# Zeus_v2.net
KiCad netlist of a schematic drawn in EAGLE
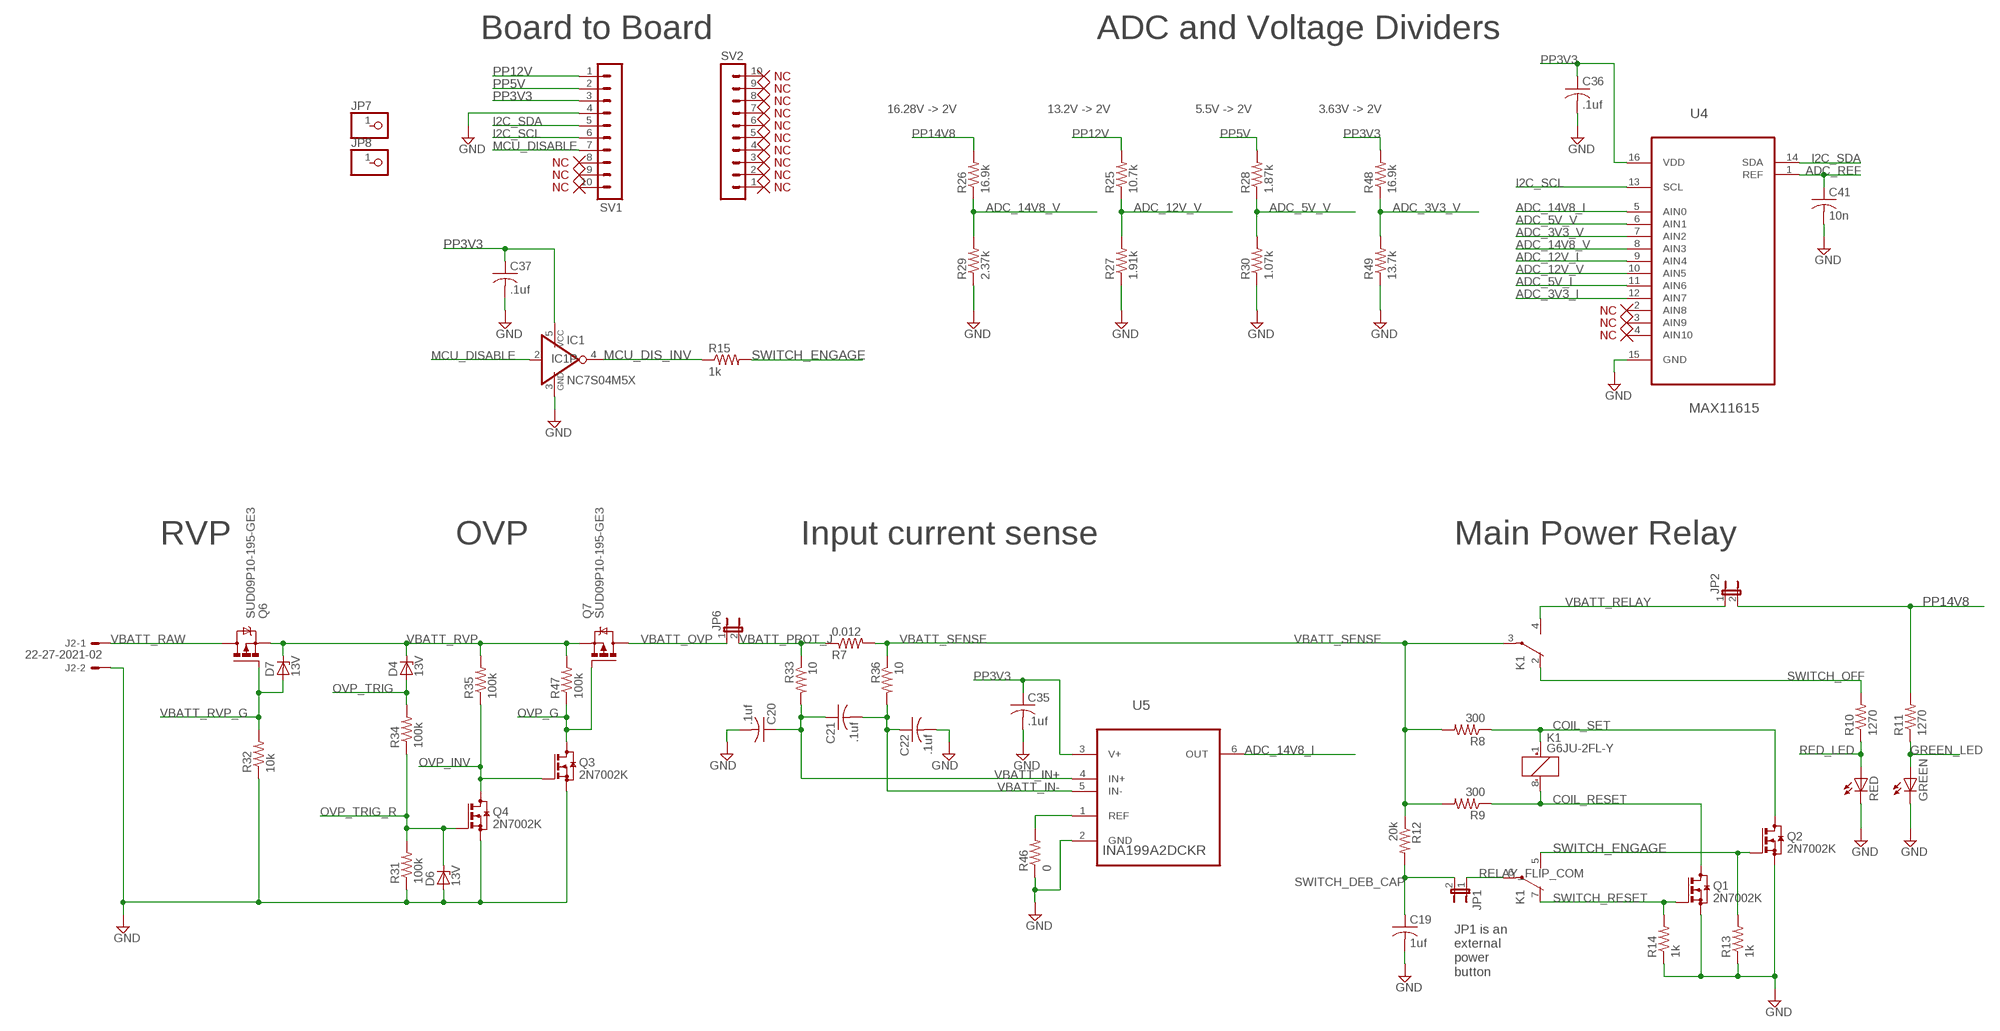
[diagram p0: schematic, sheet 1, part 1 of 2]
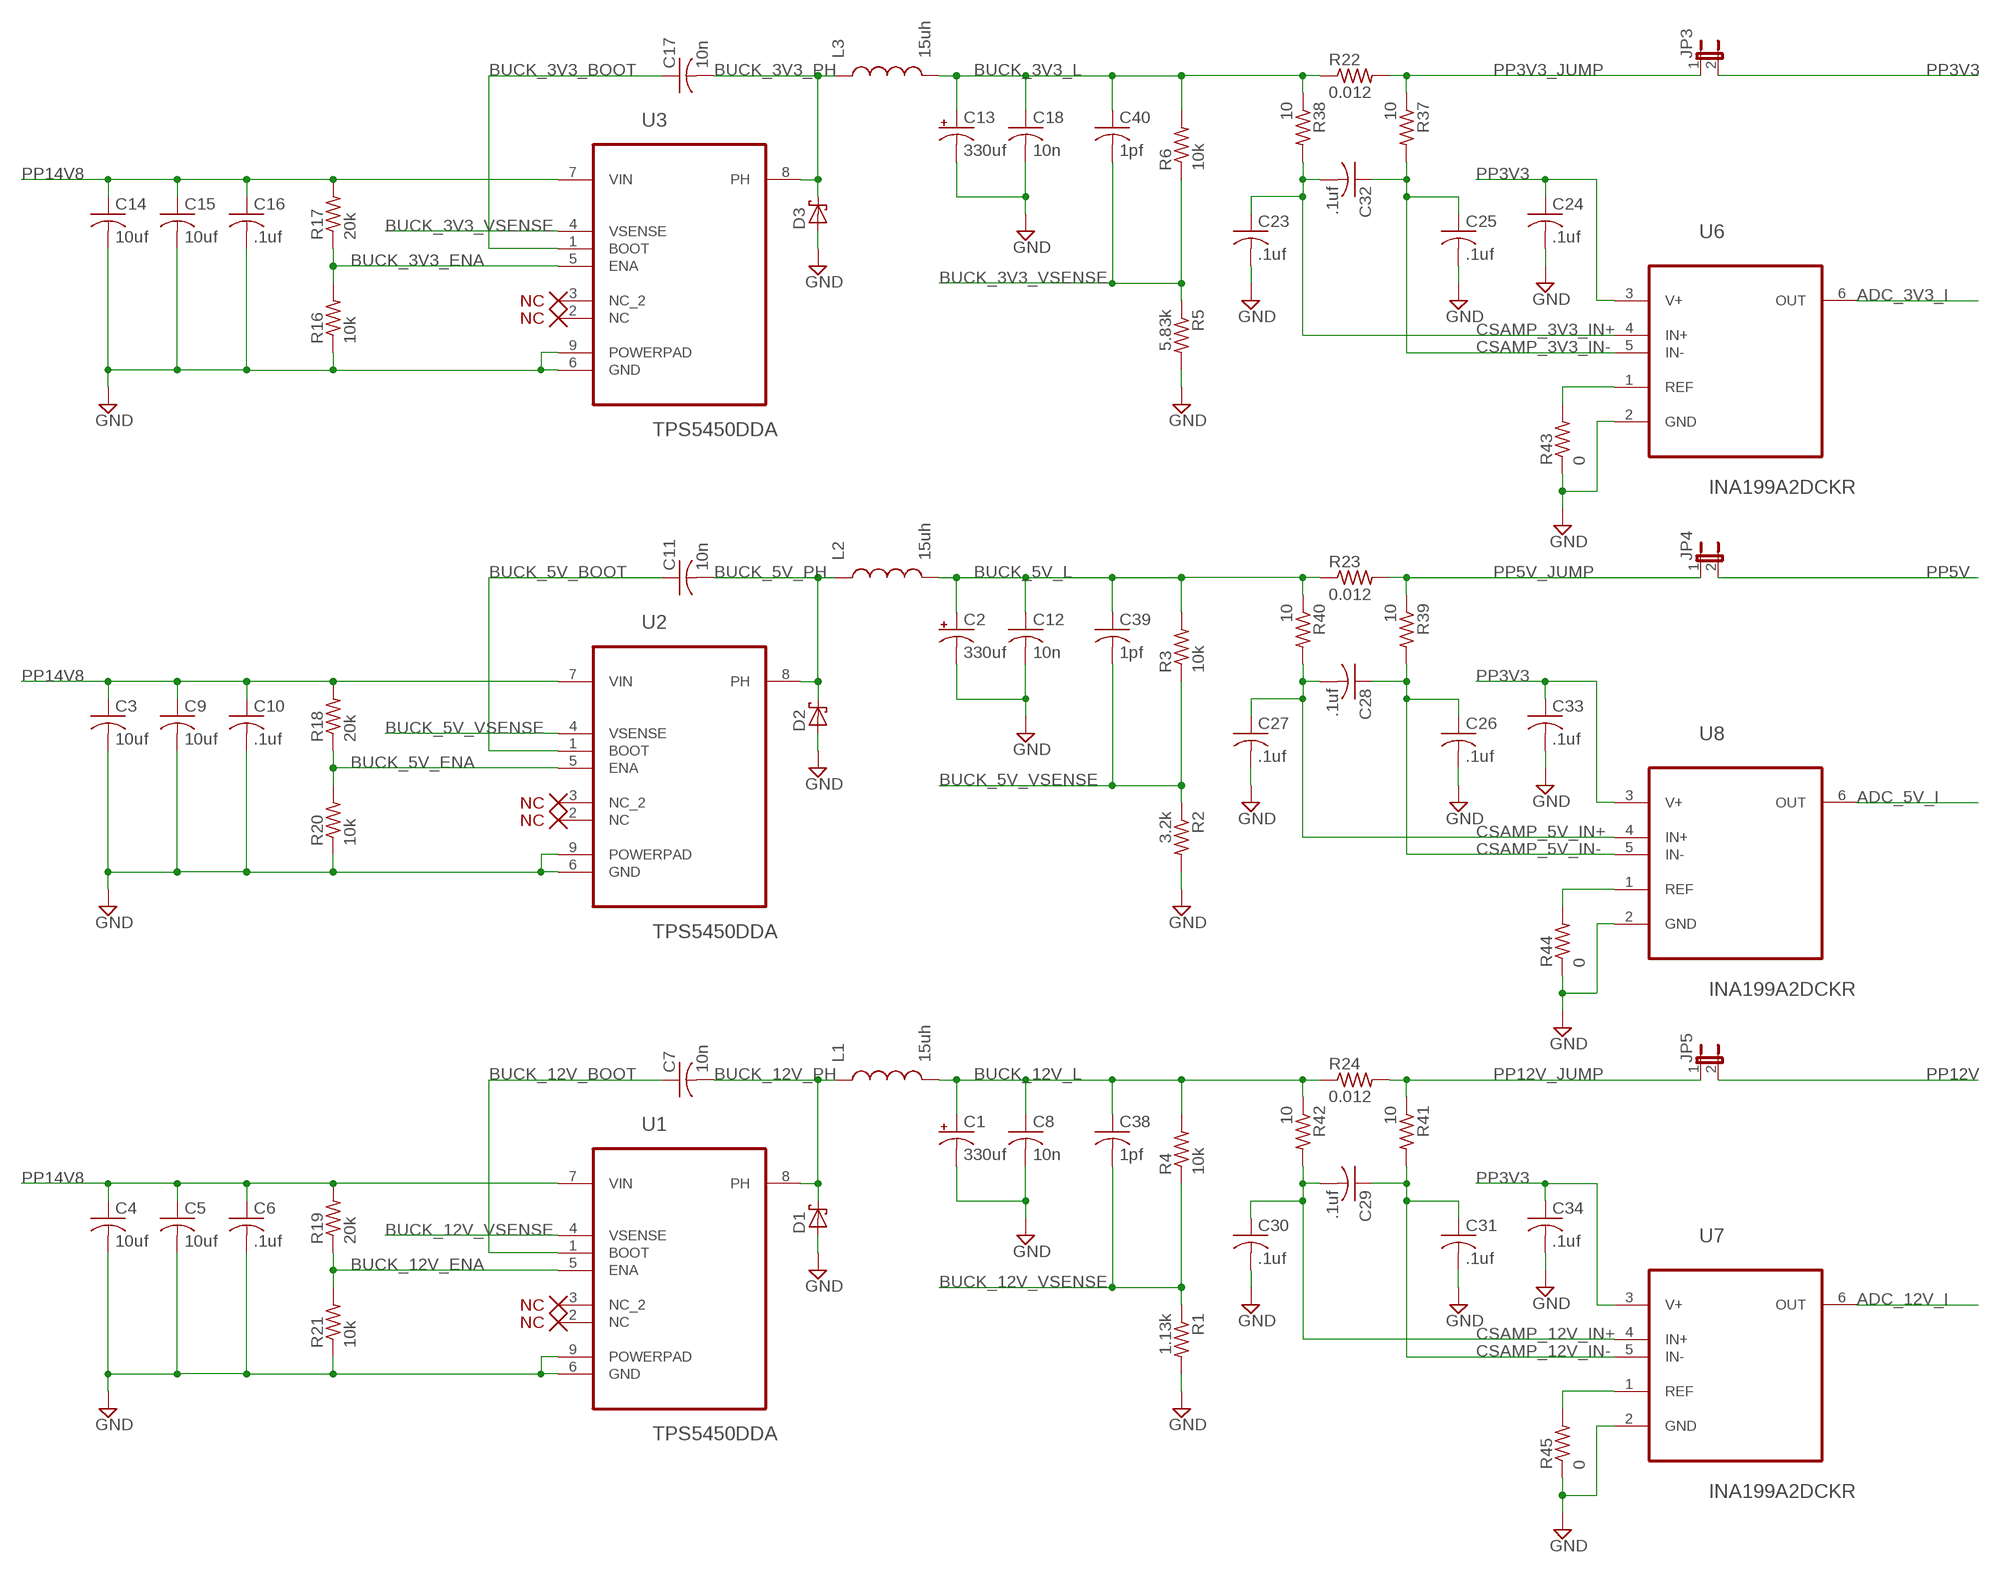
[diagram p1: schematic, sheet 1, part 2 of 2]

(export (version "E")
  (design (tool "Eeschema 10.0.6"))
  (components
    (comp (ref "C1")
      (value "330uf")
      (footprint "eagle-import:153CLV-0605")
      (libsource (lib "eagle-import") (part "CPOL-US153CLV-0605"))
    )
    (comp (ref "C2")
      (value "330uf")
      (footprint "eagle-import:153CLV-0605")
      (libsource (lib "eagle-import") (part "CPOL-US153CLV-0605"))
    )
    (comp (ref "C3")
      (value "10uf")
      (footprint "eagle-import:C1206")
      (libsource (lib "eagle-import") (part "C-USC1206"))
    )
    (comp (ref "C4")
      (value "10uf")
      (footprint "eagle-import:C1206")
      (libsource (lib "eagle-import") (part "C-USC1206"))
    )
    (comp (ref "C5")
      (value "10uf")
      (footprint "eagle-import:C1206")
      (libsource (lib "eagle-import") (part "C-USC1206"))
    )
    (comp (ref "C6")
      (value ".1uf")
      (footprint "eagle-import:C0402")
      (libsource (lib "eagle-import") (part "C-USC0402"))
    )
    (comp (ref "C7")
      (value "10n")
      (footprint "eagle-import:C0402")
      (libsource (lib "eagle-import") (part "C-USC0402"))
    )
    (comp (ref "C8")
      (value "10n")
      (footprint "eagle-import:C0402")
      (libsource (lib "eagle-import") (part "C-USC0402"))
    )
    (comp (ref "C9")
      (value "10uf")
      (footprint "eagle-import:C1206")
      (libsource (lib "eagle-import") (part "C-USC1206"))
    )
    (comp (ref "C10")
      (value ".1uf")
      (footprint "eagle-import:C0402")
      (libsource (lib "eagle-import") (part "C-USC0402"))
    )
    (comp (ref "C11")
      (value "10n")
      (footprint "eagle-import:C0402")
      (libsource (lib "eagle-import") (part "C-USC0402"))
    )
    (comp (ref "C12")
      (value "10n")
      (footprint "eagle-import:C0402")
      (libsource (lib "eagle-import") (part "C-USC0402"))
    )
    (comp (ref "C13")
      (value "330uf")
      (footprint "eagle-import:153CLV-0605")
      (libsource (lib "eagle-import") (part "CPOL-US153CLV-0605"))
    )
    (comp (ref "C14")
      (value "10uf")
      (footprint "eagle-import:C1206")
      (libsource (lib "eagle-import") (part "C-USC1206"))
    )
    (comp (ref "C15")
      (value "10uf")
      (footprint "eagle-import:C1206")
      (libsource (lib "eagle-import") (part "C-USC1206"))
    )
    (comp (ref "C16")
      (value ".1uf")
      (footprint "eagle-import:C0402")
      (libsource (lib "eagle-import") (part "C-USC0402"))
    )
    (comp (ref "C17")
      (value "10n")
      (footprint "eagle-import:C0402")
      (libsource (lib "eagle-import") (part "C-USC0402"))
    )
    (comp (ref "C18")
      (value "10n")
      (footprint "eagle-import:C0402")
      (libsource (lib "eagle-import") (part "C-USC0402"))
    )
    (comp (ref "C19")
      (value "1uf")
      (footprint "eagle-import:C0603")
      (libsource (lib "eagle-import") (part "C-USC0603"))
    )
    (comp (ref "C20")
      (value ".1uf")
      (footprint "eagle-import:C0402")
      (libsource (lib "eagle-import") (part "C-USC0402"))
    )
    (comp (ref "C21")
      (value ".1uf")
      (footprint "eagle-import:C0402")
      (libsource (lib "eagle-import") (part "C-USC0402"))
    )
    (comp (ref "C22")
      (value ".1uf")
      (footprint "eagle-import:C0402")
      (libsource (lib "eagle-import") (part "C-USC0402"))
    )
    (comp (ref "C23")
      (value ".1uf")
      (footprint "eagle-import:C0402")
      (libsource (lib "eagle-import") (part "C-USC0402"))
    )
    (comp (ref "C24")
      (value ".1uf")
      (footprint "eagle-import:C0402")
      (libsource (lib "eagle-import") (part "C-USC0402"))
    )
    (comp (ref "C25")
      (value ".1uf")
      (footprint "eagle-import:C0402")
      (libsource (lib "eagle-import") (part "C-USC0402"))
    )
    (comp (ref "C26")
      (value ".1uf")
      (footprint "eagle-import:C0402")
      (libsource (lib "eagle-import") (part "C-USC0402"))
    )
    (comp (ref "C27")
      (value ".1uf")
      (footprint "eagle-import:C0402")
      (libsource (lib "eagle-import") (part "C-USC0402"))
    )
    (comp (ref "C28")
      (value ".1uf")
      (footprint "eagle-import:C0402")
      (libsource (lib "eagle-import") (part "C-USC0402"))
    )
    (comp (ref "C29")
      (value ".1uf")
      (footprint "eagle-import:C0402")
      (libsource (lib "eagle-import") (part "C-USC0402"))
    )
    (comp (ref "C30")
      (value ".1uf")
      (footprint "eagle-import:C0402")
      (libsource (lib "eagle-import") (part "C-USC0402"))
    )
    (comp (ref "C31")
      (value ".1uf")
      (footprint "eagle-import:C0402")
      (libsource (lib "eagle-import") (part "C-USC0402"))
    )
    (comp (ref "C32")
      (value ".1uf")
      (footprint "eagle-import:C0402")
      (libsource (lib "eagle-import") (part "C-USC0402"))
    )
    (comp (ref "C33")
      (value ".1uf")
      (footprint "eagle-import:C0402")
      (libsource (lib "eagle-import") (part "C-USC0402"))
    )
    (comp (ref "C34")
      (value ".1uf")
      (footprint "eagle-import:C0402")
      (libsource (lib "eagle-import") (part "C-USC0402"))
    )
    (comp (ref "C35")
      (value ".1uf")
      (footprint "eagle-import:C0402")
      (libsource (lib "eagle-import") (part "C-USC0402"))
    )
    (comp (ref "C36")
      (value ".1uf")
      (footprint "eagle-import:C0402")
      (libsource (lib "eagle-import") (part "C-USC0402"))
    )
    (comp (ref "C37")
      (value ".1uf")
      (footprint "eagle-import:C0402")
      (libsource (lib "eagle-import") (part "C-USC0402"))
    )
    (comp (ref "C38")
      (value "1pf")
      (footprint "eagle-import:C0402")
      (libsource (lib "eagle-import") (part "C-USC0402"))
    )
    (comp (ref "C39")
      (value "1pf")
      (footprint "eagle-import:C0402")
      (libsource (lib "eagle-import") (part "C-USC0402"))
    )
    (comp (ref "C40")
      (value "1pf")
      (footprint "eagle-import:C0402")
      (libsource (lib "eagle-import") (part "C-USC0402"))
    )
    (comp (ref "C41")
      (value "10n")
      (footprint "eagle-import:C0402")
      (libsource (lib "eagle-import") (part "C-USC0402"))
    )
    (comp (ref "D1")
      (value "SCHOTTKY-DIODESMC")
      (footprint "eagle-import:SMC")
      (libsource (lib "eagle-import") (part "SCHOTTKY-DIODESMC"))
    )
    (comp (ref "D2")
      (value "SCHOTTKY-DIODESMC")
      (footprint "eagle-import:SMC")
      (libsource (lib "eagle-import") (part "SCHOTTKY-DIODESMC"))
    )
    (comp (ref "D3")
      (value "SCHOTTKY-DIODESMC")
      (footprint "eagle-import:SMC")
      (libsource (lib "eagle-import") (part "SCHOTTKY-DIODESMC"))
    )
    (comp (ref "D4")
      (value "13V")
      (footprint "eagle-import:SOT23")
      (libsource (lib "eagle-import") (part "ZENER-DIODESOT23"))
    )
    (comp (ref "D6")
      (value "13V")
      (footprint "eagle-import:SOT23")
      (libsource (lib "eagle-import") (part "ZENER-DIODESOT23"))
    )
    (comp (ref "D7")
      (value "13V")
      (footprint "eagle-import:SOT23")
      (libsource (lib "eagle-import") (part "ZENER-DIODESOT23"))
    )
    (comp (ref "GREEN")
      (value "LED_ESML0603")
      (footprint "eagle-import:LED_SML0603")
      (libsource (lib "eagle-import") (part "LED_ESML0603"))
    )
    (comp (ref "IC1")
      (value "NC7S04M5X")
      (footprint "eagle-import:SOT23-5")
      (libsource (lib "eagle-import") (part "741G06DBVAUC"))
    )
    (comp (ref "J2")
      (value "22-27-2021-02")
      (footprint "eagle-import:6410-02")
      (libsource (lib "eagle-import") (part "22-?-0227-2021"))
    )
    (comp (ref "JP1")
      (value "JP1E")
      (footprint "eagle-import:JP1")
      (libsource (lib "eagle-import") (part "JP1E"))
    )
    (comp (ref "JP2")
      (value "JP1E")
      (footprint "eagle-import:JP1")
      (libsource (lib "eagle-import") (part "JP1E"))
    )
    (comp (ref "JP3")
      (value "JP1E")
      (footprint "eagle-import:JP1")
      (libsource (lib "eagle-import") (part "JP1E"))
    )
    (comp (ref "JP4")
      (value "JP1E")
      (footprint "eagle-import:JP1")
      (libsource (lib "eagle-import") (part "JP1E"))
    )
    (comp (ref "JP5")
      (value "JP1E")
      (footprint "eagle-import:JP1")
      (libsource (lib "eagle-import") (part "JP1E"))
    )
    (comp (ref "JP6")
      (value "JP1E")
      (footprint "eagle-import:JP1")
      (libsource (lib "eagle-import") (part "JP1E"))
    )
    (comp (ref "JP7")
      (value "PINHD-1X1")
      (footprint "eagle-import:1X01")
      (libsource (lib "eagle-import") (part "PINHD-1X1"))
    )
    (comp (ref "JP8")
      (value "PINHD-1X1")
      (footprint "eagle-import:1X01")
      (libsource (lib "eagle-import") (part "PINHD-1X1"))
    )
    (comp (ref "K1")
      (value "G6JU-2FL-Y")
      (footprint "eagle-import:G6J-2FL-Y")
      (fields (field (name "MPN") "G6JU-2FL-Y DC3"))
      (libsource (lib "eagle-import") (part "G6J-2?-YFLU"))
    )
    (comp (ref "L1")
      (value "15uh")
      (footprint "eagle-import:SUMIDA")
      (libsource (lib "eagle-import") (part "INDUCTOR"))
    )
    (comp (ref "L2")
      (value "15uh")
      (footprint "eagle-import:SUMIDA")
      (libsource (lib "eagle-import") (part "INDUCTOR"))
    )
    (comp (ref "L3")
      (value "15uh")
      (footprint "eagle-import:SUMIDA")
      (libsource (lib "eagle-import") (part "INDUCTOR"))
    )
    (comp (ref "Q1")
      (value "2N7002K")
      (footprint "eagle-import:SOT23")
      (libsource (lib "eagle-import") (part "BSS123"))
    )
    (comp (ref "Q2")
      (value "2N7002K")
      (footprint "eagle-import:SOT23")
      (libsource (lib "eagle-import") (part "BSS123"))
    )
    (comp (ref "Q3")
      (value "2N7002K")
      (footprint "eagle-import:SOT23")
      (libsource (lib "eagle-import") (part "BSS123"))
    )
    (comp (ref "Q4")
      (value "2N7002K")
      (footprint "eagle-import:SOT23")
      (libsource (lib "eagle-import") (part "BSS123"))
    )
    (comp (ref "Q6")
      (value "SUD09P10-195-GE3")
      (footprint "eagle-import:D-PAK_TO252AA")
      (libsource (lib "eagle-import") (part "IRF?5305R"))
    )
    (comp (ref "Q7")
      (value "SUD09P10-195-GE3")
      (footprint "eagle-import:D-PAK_TO252AA")
      (libsource (lib "eagle-import") (part "IRF?5305R"))
    )
    (comp (ref "R1")
      (value "1.13k")
      (footprint "eagle-import:R0603")
      (libsource (lib "eagle-import") (part "R-US_R0603"))
    )
    (comp (ref "R2")
      (value "3.2k")
      (footprint "eagle-import:R0603")
      (libsource (lib "eagle-import") (part "R-US_R0603"))
    )
    (comp (ref "R3")
      (value "10k")
      (footprint "eagle-import:R0603")
      (libsource (lib "eagle-import") (part "R-US_R0603"))
    )
    (comp (ref "R4")
      (value "10k")
      (footprint "eagle-import:R0603")
      (libsource (lib "eagle-import") (part "R-US_R0603"))
    )
    (comp (ref "R5")
      (value "5.83k")
      (footprint "eagle-import:R0603")
      (libsource (lib "eagle-import") (part "R-US_R0603"))
    )
    (comp (ref "R6")
      (value "10k")
      (footprint "eagle-import:R0603")
      (libsource (lib "eagle-import") (part "R-US_R0603"))
    )
    (comp (ref "R7")
      (value "0.012")
      (footprint "eagle-import:R0805")
      (libsource (lib "eagle-import") (part "resistor_R-US_R0805"))
    )
    (comp (ref "R8")
      (value "300")
      (footprint "eagle-import:R0603")
      (libsource (lib "eagle-import") (part "R-US_R0603"))
    )
    (comp (ref "R9")
      (value "300")
      (footprint "eagle-import:R0603")
      (libsource (lib "eagle-import") (part "R-US_R0603"))
    )
    (comp (ref "R10")
      (value "1270")
      (footprint "eagle-import:R0603")
      (libsource (lib "eagle-import") (part "R-US_R0603"))
    )
    (comp (ref "R11")
      (value "1270")
      (footprint "eagle-import:R0603")
      (libsource (lib "eagle-import") (part "R-US_R0603"))
    )
    (comp (ref "R12")
      (value "20k")
      (footprint "eagle-import:R0603")
      (libsource (lib "eagle-import") (part "R-US_R0603"))
    )
    (comp (ref "R13")
      (value "1k")
      (footprint "eagle-import:R0603")
      (libsource (lib "eagle-import") (part "R-US_R0603"))
    )
    (comp (ref "R14")
      (value "1k")
      (footprint "eagle-import:R0603")
      (libsource (lib "eagle-import") (part "R-US_R0603"))
    )
    (comp (ref "R15")
      (value "1k")
      (footprint "eagle-import:R0603")
      (libsource (lib "eagle-import") (part "R-US_R0603"))
    )
    (comp (ref "R16")
      (value "10k")
      (footprint "eagle-import:R0603")
      (libsource (lib "eagle-import") (part "R-US_R0603"))
    )
    (comp (ref "R17")
      (value "20k")
      (footprint "eagle-import:R0603")
      (libsource (lib "eagle-import") (part "R-US_R0603"))
    )
    (comp (ref "R18")
      (value "20k")
      (footprint "eagle-import:R0603")
      (libsource (lib "eagle-import") (part "R-US_R0603"))
    )
    (comp (ref "R19")
      (value "20k")
      (footprint "eagle-import:R0603")
      (libsource (lib "eagle-import") (part "R-US_R0603"))
    )
    (comp (ref "R20")
      (value "10k")
      (footprint "eagle-import:R0603")
      (libsource (lib "eagle-import") (part "R-US_R0603"))
    )
    (comp (ref "R21")
      (value "10k")
      (footprint "eagle-import:R0603")
      (libsource (lib "eagle-import") (part "R-US_R0603"))
    )
    (comp (ref "R22")
      (value "0.012")
      (footprint "eagle-import:R0805")
      (libsource (lib "eagle-import") (part "resistor_R-US_R0805"))
    )
    (comp (ref "R23")
      (value "0.012")
      (footprint "eagle-import:R0805")
      (libsource (lib "eagle-import") (part "resistor_R-US_R0805"))
    )
    (comp (ref "R24")
      (value "0.012")
      (footprint "eagle-import:R0805")
      (libsource (lib "eagle-import") (part "resistor_R-US_R0805"))
    )
    (comp (ref "R25")
      (value "10.7k")
      (footprint "eagle-import:R0603")
      (libsource (lib "eagle-import") (part "R-US_R0603"))
    )
    (comp (ref "R26")
      (value "16.9k")
      (footprint "eagle-import:R0603")
      (libsource (lib "eagle-import") (part "resistor_R-US_R0603"))
    )
    (comp (ref "R27")
      (value "1.91k")
      (footprint "eagle-import:R0603")
      (libsource (lib "eagle-import") (part "R-US_R0603"))
    )
    (comp (ref "R28")
      (value "1.87k")
      (footprint "eagle-import:R0603")
      (libsource (lib "eagle-import") (part "R-US_R0603"))
    )
    (comp (ref "R29")
      (value "2.37k")
      (footprint "eagle-import:R0603")
      (libsource (lib "eagle-import") (part "resistor_R-US_R0603"))
    )
    (comp (ref "R30")
      (value "1.07k")
      (footprint "eagle-import:R0603")
      (libsource (lib "eagle-import") (part "R-US_R0603"))
    )
    (comp (ref "R31")
      (value "100k")
      (footprint "eagle-import:R0603")
      (libsource (lib "eagle-import") (part "R-US_R0603"))
    )
    (comp (ref "R32")
      (value "10k")
      (footprint "eagle-import:R0603")
      (libsource (lib "eagle-import") (part "R-US_R0603"))
    )
    (comp (ref "R33")
      (value "10")
      (footprint "eagle-import:R0603")
      (libsource (lib "eagle-import") (part "R-US_R0603"))
    )
    (comp (ref "R34")
      (value "100k")
      (footprint "eagle-import:R0603")
      (libsource (lib "eagle-import") (part "R-US_R0603"))
    )
    (comp (ref "R35")
      (value "100k")
      (footprint "eagle-import:R0603")
      (libsource (lib "eagle-import") (part "R-US_R0603"))
    )
    (comp (ref "R36")
      (value "10")
      (footprint "eagle-import:R0603")
      (libsource (lib "eagle-import") (part "R-US_R0603"))
    )
    (comp (ref "R37")
      (value "10")
      (footprint "eagle-import:R0603")
      (libsource (lib "eagle-import") (part "R-US_R0603"))
    )
    (comp (ref "R38")
      (value "10")
      (footprint "eagle-import:R0603")
      (libsource (lib "eagle-import") (part "R-US_R0603"))
    )
    (comp (ref "R39")
      (value "10")
      (footprint "eagle-import:R0603")
      (libsource (lib "eagle-import") (part "R-US_R0603"))
    )
    (comp (ref "R40")
      (value "10")
      (footprint "eagle-import:R0603")
      (libsource (lib "eagle-import") (part "R-US_R0603"))
    )
    (comp (ref "R41")
      (value "10")
      (footprint "eagle-import:R0603")
      (libsource (lib "eagle-import") (part "R-US_R0603"))
    )
    (comp (ref "R42")
      (value "10")
      (footprint "eagle-import:R0603")
      (libsource (lib "eagle-import") (part "R-US_R0603"))
    )
    (comp (ref "R43")
      (value "0")
      (footprint "eagle-import:R0603")
      (libsource (lib "eagle-import") (part "R-US_R0603"))
    )
    (comp (ref "R44")
      (value "0")
      (footprint "eagle-import:R0603")
      (libsource (lib "eagle-import") (part "R-US_R0603"))
    )
    (comp (ref "R45")
      (value "0")
      (footprint "eagle-import:R0603")
      (libsource (lib "eagle-import") (part "R-US_R0603"))
    )
    (comp (ref "R46")
      (value "0")
      (footprint "eagle-import:R0603")
      (libsource (lib "eagle-import") (part "R-US_R0603"))
    )
    (comp (ref "R47")
      (value "100k")
      (footprint "eagle-import:R0603")
      (libsource (lib "eagle-import") (part "R-US_R0603"))
    )
    (comp (ref "R48")
      (value "16.9k")
      (footprint "eagle-import:R0603")
      (libsource (lib "eagle-import") (part "R-US_R0603"))
    )
    (comp (ref "R49")
      (value "13.7k")
      (footprint "eagle-import:R0603")
      (libsource (lib "eagle-import") (part "R-US_R0603"))
    )
    (comp (ref "RED")
      (value "LED_ESML0603")
      (footprint "eagle-import:LED_SML0603")
      (libsource (lib "eagle-import") (part "LED_ESML0603"))
    )
    (comp (ref "SV1")
      (value "MA10-1")
      (footprint "eagle-import:MA10-1")
      (libsource (lib "eagle-import") (part "MA10-1"))
    )
    (comp (ref "SV2")
      (value "MA10-1")
      (footprint "eagle-import:MA10-1")
      (libsource (lib "eagle-import") (part "MA10-1"))
    )
    (comp (ref "U1")
      (value "TPS5450DDA")
      (footprint "eagle-import:SOIC127P600X170-9N")
      (libsource (lib "eagle-import") (part "TPS5450DDA"))
    )
    (comp (ref "U2")
      (value "TPS5450DDA")
      (footprint "eagle-import:SOIC127P600X170-9N")
      (libsource (lib "eagle-import") (part "TPS5450DDA"))
    )
    (comp (ref "U3")
      (value "TPS5450DDA")
      (footprint "eagle-import:SOIC127P600X170-9N")
      (libsource (lib "eagle-import") (part "TPS5450DDA"))
    )
    (comp (ref "U4")
      (value "MAX11615")
      (footprint "eagle-import:SOP63P600X175-16N")
      (fields (field (name "MPN") "MAX11602EEE+T"))
      (libsource (lib "eagle-import") (part "MAX11602EEE+T"))
    )
    (comp (ref "U5")
      (value "INA199A2DCKR")
      (footprint "eagle-import:SOT65P210X110-6N")
      (libsource (lib "eagle-import") (part "INA199A2DCKR"))
    )
    (comp (ref "U6")
      (value "INA199A2DCKR")
      (footprint "eagle-import:SOT65P210X110-6N")
      (libsource (lib "eagle-import") (part "INA199A2DCKR"))
    )
    (comp (ref "U7")
      (value "INA199A2DCKR")
      (footprint "eagle-import:SOT65P210X110-6N")
      (libsource (lib "eagle-import") (part "INA199A2DCKR"))
    )
    (comp (ref "U8")
      (value "INA199A2DCKR")
      (footprint "eagle-import:SOT65P210X110-6N")
      (libsource (lib "eagle-import") (part "INA199A2DCKR"))
    )
  )
  (nets
    (net (code "1") (name "/ADC_3V3_I") (class "Default")
      (node (ref "U4") (pin "12") (pinfunction "AIN7_12") (pintype "input"))
      (node (ref "U6") (pin "6") (pinfunction "OUT_6") (pintype "output"))
    )
    (net (code "2") (name "/ADC_3V3_V") (class "Default")
      (node (ref "R48") (pin "1") (pinfunction "1_1") (pintype "passive"))
      (node (ref "R49") (pin "2") (pinfunction "2_2") (pintype "passive"))
      (node (ref "U4") (pin "7") (pinfunction "AIN2_7") (pintype "input"))
    )
    (net (code "3") (name "/ADC_5V_I") (class "Default")
      (node (ref "U4") (pin "11") (pinfunction "AIN6_11") (pintype "input"))
      (node (ref "U8") (pin "6") (pinfunction "OUT_6") (pintype "output"))
    )
    (net (code "4") (name "/ADC_5V_V") (class "Default")
      (node (ref "R28") (pin "1") (pinfunction "1_1") (pintype "passive"))
      (node (ref "R30") (pin "2") (pinfunction "2_2") (pintype "passive"))
      (node (ref "U4") (pin "6") (pinfunction "AIN1_6") (pintype "input"))
    )
    (net (code "5") (name "/ADC_12V_I") (class "Default")
      (node (ref "U4") (pin "9") (pinfunction "AIN4_9") (pintype "input"))
      (node (ref "U7") (pin "6") (pinfunction "OUT_6") (pintype "output"))
    )
    (net (code "6") (name "/ADC_12V_V") (class "Default")
      (node (ref "R25") (pin "1") (pinfunction "1_1") (pintype "passive"))
      (node (ref "R27") (pin "2") (pinfunction "2_2") (pintype "passive"))
      (node (ref "U4") (pin "10") (pinfunction "AIN5_10") (pintype "input"))
    )
    (net (code "7") (name "/ADC_14V8_I") (class "Default")
      (node (ref "U4") (pin "5") (pinfunction "AIN0_5") (pintype "input"))
      (node (ref "U5") (pin "6") (pinfunction "OUT_6") (pintype "output"))
    )
    (net (code "8") (name "/ADC_14V8_V") (class "Default")
      (node (ref "R26") (pin "1") (pinfunction "1_1") (pintype "passive"))
      (node (ref "R29") (pin "2") (pinfunction "2_2") (pintype "passive"))
      (node (ref "U4") (pin "8") (pinfunction "AIN3_8") (pintype "input"))
    )
    (net (code "9") (name "/ADC_REF") (class "Default")
      (node (ref "C41") (pin "1") (pinfunction "1_1") (pintype "passive"))
      (node (ref "U4") (pin "1") (pinfunction "REF_1") (pintype "bidirectional"))
    )
    (net (code "10") (name "/BUCK_3V3_BOOT") (class "Default")
      (node (ref "C17") (pin "1") (pinfunction "1_1") (pintype "passive"))
      (node (ref "U3") (pin "1") (pinfunction "BOOT_1") (pintype "input"))
    )
    (net (code "11") (name "/BUCK_3V3_ENA") (class "Default")
      (node (ref "R16") (pin "2") (pinfunction "2_2") (pintype "passive"))
      (node (ref "R17") (pin "1") (pinfunction "1_1") (pintype "passive"))
      (node (ref "U3") (pin "5") (pinfunction "ENA_5") (pintype "input"))
    )
    (net (code "12") (name "/BUCK_3V3_L") (class "Default")
      (node (ref "C13") (pin "+") (pinfunction "+_+") (pintype "passive"))
      (node (ref "C18") (pin "1") (pinfunction "1_1") (pintype "passive"))
      (node (ref "C40") (pin "1") (pinfunction "1_1") (pintype "passive"))
      (node (ref "L3") (pin "P$2") (pinfunction "2_P$2") (pintype "passive"))
      (node (ref "R22") (pin "1") (pinfunction "1_1") (pintype "passive"))
      (node (ref "R38") (pin "1") (pinfunction "1_1") (pintype "passive"))
      (node (ref "R6") (pin "2") (pinfunction "2_2") (pintype "passive"))
    )
    (net (code "13") (name "/BUCK_3V3_PH") (class "Default")
      (node (ref "C17") (pin "2") (pinfunction "2_2") (pintype "passive"))
      (node (ref "D3") (pin "C") (pinfunction "C_C") (pintype "passive"))
      (node (ref "L3") (pin "P$1") (pinfunction "1_P$1") (pintype "passive"))
      (node (ref "U3") (pin "8") (pinfunction "PH_8") (pintype "output"))
    )
    (net (code "14") (name "/BUCK_3V3_VSENSE") (class "Default")
      (node (ref "C40") (pin "2") (pinfunction "2_2") (pintype "passive"))
      (node (ref "R5") (pin "1") (pinfunction "1_1") (pintype "passive"))
      (node (ref "R6") (pin "1") (pinfunction "1_1") (pintype "passive"))
      (node (ref "U3") (pin "4") (pinfunction "VSENSE_4") (pintype "input"))
    )
    (net (code "15") (name "/BUCK_5V_BOOT") (class "Default")
      (node (ref "C11") (pin "1") (pinfunction "1_1") (pintype "passive"))
      (node (ref "U2") (pin "1") (pinfunction "BOOT_1") (pintype "input"))
    )
    (net (code "16") (name "/BUCK_5V_ENA") (class "Default")
      (node (ref "R18") (pin "1") (pinfunction "1_1") (pintype "passive"))
      (node (ref "R20") (pin "2") (pinfunction "2_2") (pintype "passive"))
      (node (ref "U2") (pin "5") (pinfunction "ENA_5") (pintype "input"))
    )
    (net (code "17") (name "/BUCK_5V_L") (class "Default")
      (node (ref "C12") (pin "1") (pinfunction "1_1") (pintype "passive"))
      (node (ref "C2") (pin "+") (pinfunction "+_+") (pintype "passive"))
      (node (ref "C39") (pin "1") (pinfunction "1_1") (pintype "passive"))
      (node (ref "L2") (pin "P$2") (pinfunction "2_P$2") (pintype "passive"))
      (node (ref "R23") (pin "1") (pinfunction "1_1") (pintype "passive"))
      (node (ref "R3") (pin "2") (pinfunction "2_2") (pintype "passive"))
      (node (ref "R40") (pin "1") (pinfunction "1_1") (pintype "passive"))
    )
    (net (code "18") (name "/BUCK_5V_PH") (class "Default")
      (node (ref "C11") (pin "2") (pinfunction "2_2") (pintype "passive"))
      (node (ref "D2") (pin "C") (pinfunction "C_C") (pintype "passive"))
      (node (ref "L2") (pin "P$1") (pinfunction "1_P$1") (pintype "passive"))
      (node (ref "U2") (pin "8") (pinfunction "PH_8") (pintype "output"))
    )
    (net (code "19") (name "/BUCK_5V_VSENSE") (class "Default")
      (node (ref "C39") (pin "2") (pinfunction "2_2") (pintype "passive"))
      (node (ref "R2") (pin "1") (pinfunction "1_1") (pintype "passive"))
      (node (ref "R3") (pin "1") (pinfunction "1_1") (pintype "passive"))
      (node (ref "U2") (pin "4") (pinfunction "VSENSE_4") (pintype "input"))
    )
    (net (code "20") (name "/BUCK_12V_BOOT") (class "Default")
      (node (ref "C7") (pin "1") (pinfunction "1_1") (pintype "passive"))
      (node (ref "U1") (pin "1") (pinfunction "BOOT_1") (pintype "input"))
    )
    (net (code "21") (name "/BUCK_12V_ENA") (class "Default")
      (node (ref "R19") (pin "1") (pinfunction "1_1") (pintype "passive"))
      (node (ref "R21") (pin "2") (pinfunction "2_2") (pintype "passive"))
      (node (ref "U1") (pin "5") (pinfunction "ENA_5") (pintype "input"))
    )
    (net (code "22") (name "/BUCK_12V_L") (class "Default")
      (node (ref "C1") (pin "+") (pinfunction "+_+") (pintype "passive"))
      (node (ref "C38") (pin "1") (pinfunction "1_1") (pintype "passive"))
      (node (ref "C8") (pin "1") (pinfunction "1_1") (pintype "passive"))
      (node (ref "L1") (pin "P$2") (pinfunction "2_P$2") (pintype "passive"))
      (node (ref "R24") (pin "1") (pinfunction "1_1") (pintype "passive"))
      (node (ref "R4") (pin "2") (pinfunction "2_2") (pintype "passive"))
      (node (ref "R42") (pin "1") (pinfunction "1_1") (pintype "passive"))
    )
    (net (code "23") (name "/BUCK_12V_PH") (class "Default")
      (node (ref "C7") (pin "2") (pinfunction "2_2") (pintype "passive"))
      (node (ref "D1") (pin "C") (pinfunction "C_C") (pintype "passive"))
      (node (ref "L1") (pin "P$1") (pinfunction "1_P$1") (pintype "passive"))
      (node (ref "U1") (pin "8") (pinfunction "PH_8") (pintype "output"))
    )
    (net (code "24") (name "/BUCK_12V_VSENSE") (class "Default")
      (node (ref "C38") (pin "2") (pinfunction "2_2") (pintype "passive"))
      (node (ref "R1") (pin "1") (pinfunction "1_1") (pintype "passive"))
      (node (ref "R4") (pin "1") (pinfunction "1_1") (pintype "passive"))
      (node (ref "U1") (pin "4") (pinfunction "VSENSE_4") (pintype "input"))
    )
    (net (code "25") (name "/COIL_RESET") (class "Default")
      (node (ref "K1") (pin "8") (pinfunction "-_8") (pintype "passive"))
      (node (ref "Q1") (pin "3") (pinfunction "D_3") (pintype "passive"))
      (node (ref "R9") (pin "1") (pinfunction "1_1") (pintype "passive"))
    )
    (net (code "26") (name "/COIL_SET") (class "Default")
      (node (ref "K1") (pin "1") (pinfunction "+_1") (pintype "passive"))
      (node (ref "Q2") (pin "3") (pinfunction "D_3") (pintype "passive"))
      (node (ref "R8") (pin "1") (pinfunction "1_1") (pintype "passive"))
    )
    (net (code "27") (name "/CSAMP_3V3_IN+") (class "Default")
      (node (ref "C23") (pin "1") (pinfunction "1_1") (pintype "passive"))
      (node (ref "C32") (pin "2") (pinfunction "2_2") (pintype "passive"))
      (node (ref "R38") (pin "2") (pinfunction "2_2") (pintype "passive"))
      (node (ref "U6") (pin "4") (pinfunction "IN+_4") (pintype "input"))
    )
    (net (code "28") (name "/CSAMP_3V3_IN-") (class "Default")
      (node (ref "C25") (pin "1") (pinfunction "1_1") (pintype "passive"))
      (node (ref "C32") (pin "1") (pinfunction "1_1") (pintype "passive"))
      (node (ref "R37") (pin "2") (pinfunction "2_2") (pintype "passive"))
      (node (ref "U6") (pin "5") (pinfunction "IN-_5") (pintype "input"))
    )
    (net (code "29") (name "/CSAMP_5V_IN+") (class "Default")
      (node (ref "C27") (pin "1") (pinfunction "1_1") (pintype "passive"))
      (node (ref "C28") (pin "2") (pinfunction "2_2") (pintype "passive"))
      (node (ref "R40") (pin "2") (pinfunction "2_2") (pintype "passive"))
      (node (ref "U8") (pin "4") (pinfunction "IN+_4") (pintype "input"))
    )
    (net (code "30") (name "/CSAMP_5V_IN-") (class "Default")
      (node (ref "C26") (pin "1") (pinfunction "1_1") (pintype "passive"))
      (node (ref "C28") (pin "1") (pinfunction "1_1") (pintype "passive"))
      (node (ref "R39") (pin "2") (pinfunction "2_2") (pintype "passive"))
      (node (ref "U8") (pin "5") (pinfunction "IN-_5") (pintype "input"))
    )
    (net (code "31") (name "/CSAMP_12V_IN+") (class "Default")
      (node (ref "C29") (pin "2") (pinfunction "2_2") (pintype "passive"))
      (node (ref "C30") (pin "1") (pinfunction "1_1") (pintype "passive"))
      (node (ref "R42") (pin "2") (pinfunction "2_2") (pintype "passive"))
      (node (ref "U7") (pin "4") (pinfunction "IN+_4") (pintype "input"))
    )
    (net (code "32") (name "/CSAMP_12V_IN-") (class "Default")
      (node (ref "C29") (pin "1") (pinfunction "1_1") (pintype "passive"))
      (node (ref "C31") (pin "1") (pinfunction "1_1") (pintype "passive"))
      (node (ref "R41") (pin "2") (pinfunction "2_2") (pintype "passive"))
      (node (ref "U7") (pin "5") (pinfunction "IN-_5") (pintype "input"))
    )
    (net (code "33") (name "/GREEN_LED") (class "Default")
      (node (ref "GREEN") (pin "A") (pinfunction "A_A") (pintype "passive"))
      (node (ref "R11") (pin "1") (pinfunction "1_1") (pintype "passive"))
    )
    (net (code "34") (name "/I2C_SCL") (class "Default")
      (node (ref "SV1") (pin "6") (pinfunction "6_6") (pintype "passive"))
      (node (ref "U4") (pin "13") (pinfunction "SCL_13") (pintype "input"))
    )
    (net (code "35") (name "/I2C_SDA") (class "Default")
      (node (ref "SV1") (pin "5") (pinfunction "5_5") (pintype "passive"))
      (node (ref "U4") (pin "14") (pinfunction "SDA_14") (pintype "bidirectional"))
    )
    (net (code "36") (name "/MCU_DISABLE") (class "Default")
      (node (ref "IC1") (pin "2") (pinfunction "I_2") (pintype "input"))
      (node (ref "SV1") (pin "7") (pinfunction "7_7") (pintype "passive"))
    )
    (net (code "37") (name "/MCU_DIS_INV") (class "Default")
      (node (ref "IC1") (pin "4") (pinfunction "O_4") (pintype "open_collector"))
      (node (ref "R15") (pin "1") (pinfunction "1_1") (pintype "passive"))
    )
    (net (code "38") (name "/OVP_G") (class "Default")
      (node (ref "Q3") (pin "3") (pinfunction "D_3") (pintype "passive"))
      (node (ref "Q7") (pin "1") (pinfunction "G_1") (pintype "passive"))
      (node (ref "R47") (pin "1") (pinfunction "1_1") (pintype "passive"))
    )
    (net (code "39") (name "/OVP_INV") (class "Default")
      (node (ref "Q3") (pin "1") (pinfunction "G_1") (pintype "passive"))
      (node (ref "Q4") (pin "3") (pinfunction "D_3") (pintype "passive"))
      (node (ref "R35") (pin "1") (pinfunction "1_1") (pintype "passive"))
    )
    (net (code "40") (name "/OVP_TRIG") (class "Default")
      (node (ref "D4") (pin "1") (pinfunction "A_1") (pintype "passive"))
      (node (ref "R34") (pin "2") (pinfunction "2_2") (pintype "passive"))
    )
    (net (code "41") (name "/OVP_TRIG_R") (class "Default")
      (node (ref "D6") (pin "3") (pinfunction "C_3") (pintype "passive"))
      (node (ref "Q4") (pin "1") (pinfunction "G_1") (pintype "passive"))
      (node (ref "R31") (pin "2") (pinfunction "2_2") (pintype "passive"))
      (node (ref "R34") (pin "1") (pinfunction "1_1") (pintype "passive"))
    )
    (net (code "42") (name "/PP3V3") (class "Default")
      (node (ref "C24") (pin "1") (pinfunction "1_1") (pintype "passive"))
      (node (ref "C33") (pin "1") (pinfunction "1_1") (pintype "passive"))
      (node (ref "C34") (pin "1") (pinfunction "1_1") (pintype "passive"))
      (node (ref "C35") (pin "1") (pinfunction "1_1") (pintype "passive"))
      (node (ref "C36") (pin "1") (pinfunction "1_1") (pintype "passive"))
      (node (ref "C37") (pin "1") (pinfunction "1_1") (pintype "passive"))
      (node (ref "IC1") (pin "5") (pinfunction "VCC_5") (pintype "power_in"))
      (node (ref "JP3") (pin "2") (pinfunction "2_2") (pintype "passive"))
      (node (ref "R48") (pin "2") (pinfunction "2_2") (pintype "passive"))
      (node (ref "SV1") (pin "3") (pinfunction "3_3") (pintype "passive"))
      (node (ref "U4") (pin "16") (pinfunction "VDD_16") (pintype "power_in"))
      (node (ref "U5") (pin "3") (pinfunction "V+_3") (pintype "power_in"))
      (node (ref "U6") (pin "3") (pinfunction "V+_3") (pintype "power_in"))
      (node (ref "U7") (pin "3") (pinfunction "V+_3") (pintype "power_in"))
      (node (ref "U8") (pin "3") (pinfunction "V+_3") (pintype "power_in"))
    )
    (net (code "43") (name "/PP3V3_JUMP") (class "Default")
      (node (ref "JP3") (pin "1") (pinfunction "1_1") (pintype "passive"))
      (node (ref "R22") (pin "2") (pinfunction "2_2") (pintype "passive"))
      (node (ref "R37") (pin "1") (pinfunction "1_1") (pintype "passive"))
    )
    (net (code "44") (name "/PP5V") (class "Default")
      (node (ref "JP4") (pin "2") (pinfunction "2_2") (pintype "passive"))
      (node (ref "R28") (pin "2") (pinfunction "2_2") (pintype "passive"))
      (node (ref "SV1") (pin "2") (pinfunction "2_2") (pintype "passive"))
    )
    (net (code "45") (name "/PP5V_JUMP") (class "Default")
      (node (ref "JP4") (pin "1") (pinfunction "1_1") (pintype "passive"))
      (node (ref "R23") (pin "2") (pinfunction "2_2") (pintype "passive"))
      (node (ref "R39") (pin "1") (pinfunction "1_1") (pintype "passive"))
    )
    (net (code "46") (name "/PP12V") (class "Default")
      (node (ref "JP5") (pin "2") (pinfunction "2_2") (pintype "passive"))
      (node (ref "R25") (pin "2") (pinfunction "2_2") (pintype "passive"))
      (node (ref "SV1") (pin "1") (pinfunction "1_1") (pintype "passive"))
    )
    (net (code "47") (name "/PP12V_JUMP") (class "Default")
      (node (ref "JP5") (pin "1") (pinfunction "1_1") (pintype "passive"))
      (node (ref "R24") (pin "2") (pinfunction "2_2") (pintype "passive"))
      (node (ref "R41") (pin "1") (pinfunction "1_1") (pintype "passive"))
    )
    (net (code "48") (name "/PP14V8") (class "Default")
      (node (ref "C10") (pin "1") (pinfunction "1_1") (pintype "passive"))
      (node (ref "C14") (pin "1") (pinfunction "1_1") (pintype "passive"))
      (node (ref "C15") (pin "1") (pinfunction "1_1") (pintype "passive"))
      (node (ref "C16") (pin "1") (pinfunction "1_1") (pintype "passive"))
      (node (ref "C3") (pin "1") (pinfunction "1_1") (pintype "passive"))
      (node (ref "C4") (pin "1") (pinfunction "1_1") (pintype "passive"))
      (node (ref "C5") (pin "1") (pinfunction "1_1") (pintype "passive"))
      (node (ref "C6") (pin "1") (pinfunction "1_1") (pintype "passive"))
      (node (ref "C9") (pin "1") (pinfunction "1_1") (pintype "passive"))
      (node (ref "JP2") (pin "2") (pinfunction "2_2") (pintype "passive"))
      (node (ref "R11") (pin "2") (pinfunction "2_2") (pintype "passive"))
      (node (ref "R17") (pin "2") (pinfunction "2_2") (pintype "passive"))
      (node (ref "R18") (pin "2") (pinfunction "2_2") (pintype "passive"))
      (node (ref "R19") (pin "2") (pinfunction "2_2") (pintype "passive"))
      (node (ref "R26") (pin "2") (pinfunction "2_2") (pintype "passive"))
      (node (ref "U1") (pin "7") (pinfunction "VIN_7") (pintype "power_in"))
      (node (ref "U2") (pin "7") (pinfunction "VIN_7") (pintype "power_in"))
      (node (ref "U3") (pin "7") (pinfunction "VIN_7") (pintype "power_in"))
    )
    (net (code "49") (name "/RED_LED") (class "Default")
      (node (ref "R10") (pin "1") (pinfunction "1_1") (pintype "passive"))
      (node (ref "RED") (pin "A") (pinfunction "A_A") (pintype "passive"))
    )
    (net (code "50") (name "/RELAY_FLIP_COM") (class "Default")
      (node (ref "JP1") (pin "1") (pinfunction "1_1") (pintype "passive"))
      (node (ref "K1") (pin "6") (pinfunction "P_6") (pintype "passive"))
    )
    (net (code "51") (name "/SWITCH_DEB_CAP") (class "Default")
      (node (ref "C19") (pin "1") (pinfunction "1_1") (pintype "passive"))
      (node (ref "JP1") (pin "2") (pinfunction "2_2") (pintype "passive"))
      (node (ref "R12") (pin "2") (pinfunction "2_2") (pintype "passive"))
    )
    (net (code "52") (name "/SWITCH_ENGAGE") (class "Default")
      (node (ref "K1") (pin "5") (pinfunction "S_5") (pintype "passive"))
      (node (ref "Q2") (pin "1") (pinfunction "G_1") (pintype "passive"))
      (node (ref "R13") (pin "2") (pinfunction "2_2") (pintype "passive"))
      (node (ref "R15") (pin "2") (pinfunction "2_2") (pintype "passive"))
    )
    (net (code "53") (name "/SWITCH_OFF") (class "Default")
      (node (ref "K1") (pin "2") (pinfunction "O_2") (pintype "passive"))
      (node (ref "R10") (pin "2") (pinfunction "2_2") (pintype "passive"))
    )
    (net (code "54") (name "/SWITCH_RESET") (class "Default")
      (node (ref "K1") (pin "7") (pinfunction "O_7") (pintype "passive"))
      (node (ref "Q1") (pin "1") (pinfunction "G_1") (pintype "passive"))
      (node (ref "R14") (pin "2") (pinfunction "2_2") (pintype "passive"))
    )
    (net (code "55") (name "/VBATT_IN+") (class "Default")
      (node (ref "C20") (pin "1") (pinfunction "1_1") (pintype "passive"))
      (node (ref "C21") (pin "1") (pinfunction "1_1") (pintype "passive"))
      (node (ref "R33") (pin "2") (pinfunction "2_2") (pintype "passive"))
      (node (ref "U5") (pin "4") (pinfunction "IN+_4") (pintype "input"))
    )
    (net (code "56") (name "/VBATT_IN-") (class "Default")
      (node (ref "C21") (pin "2") (pinfunction "2_2") (pintype "passive"))
      (node (ref "C22") (pin "1") (pinfunction "1_1") (pintype "passive"))
      (node (ref "R36") (pin "2") (pinfunction "2_2") (pintype "passive"))
      (node (ref "U5") (pin "5") (pinfunction "IN-_5") (pintype "input"))
    )
    (net (code "57") (name "/VBATT_OVP") (class "Default")
      (node (ref "JP6") (pin "1") (pinfunction "1_1") (pintype "passive"))
      (node (ref "Q7") (pin "4") (pinfunction "D_4") (pintype "passive"))
    )
    (net (code "58") (name "/VBATT_PROT_J") (class "Default")
      (node (ref "JP6") (pin "2") (pinfunction "2_2") (pintype "passive"))
      (node (ref "R33") (pin "1") (pinfunction "1_1") (pintype "passive"))
      (node (ref "R7") (pin "1") (pinfunction "1_1") (pintype "passive"))
    )
    (net (code "59") (name "/VBATT_RAW") (class "Default")
      (node (ref "J2") (pin "1") (pinfunction "S_1") (pintype "passive"))
      (node (ref "Q6") (pin "4") (pinfunction "D_4") (pintype "passive"))
    )
    (net (code "60") (name "/VBATT_RELAY") (class "Default")
      (node (ref "JP2") (pin "1") (pinfunction "1_1") (pintype "passive"))
      (node (ref "K1") (pin "4") (pinfunction "S_4") (pintype "passive"))
    )
    (net (code "61") (name "/VBATT_RVP") (class "Default")
      (node (ref "D4") (pin "3") (pinfunction "C_3") (pintype "passive"))
      (node (ref "D7") (pin "3") (pinfunction "C_3") (pintype "passive"))
      (node (ref "Q6") (pin "3") (pinfunction "S_3") (pintype "passive"))
      (node (ref "Q7") (pin "3") (pinfunction "S_3") (pintype "passive"))
      (node (ref "R35") (pin "2") (pinfunction "2_2") (pintype "passive"))
      (node (ref "R47") (pin "2") (pinfunction "2_2") (pintype "passive"))
    )
    (net (code "62") (name "/VBATT_RVP_G") (class "Default")
      (node (ref "D7") (pin "1") (pinfunction "A_1") (pintype "passive"))
      (node (ref "Q6") (pin "1") (pinfunction "G_1") (pintype "passive"))
      (node (ref "R32") (pin "2") (pinfunction "2_2") (pintype "passive"))
    )
    (net (code "63") (name "/VBATT_SENSE") (class "Default")
      (node (ref "K1") (pin "3") (pinfunction "P_3") (pintype "passive"))
      (node (ref "R12") (pin "1") (pinfunction "1_1") (pintype "passive"))
      (node (ref "R36") (pin "1") (pinfunction "1_1") (pintype "passive"))
      (node (ref "R7") (pin "2") (pinfunction "2_2") (pintype "passive"))
      (node (ref "R8") (pin "2") (pinfunction "2_2") (pintype "passive"))
      (node (ref "R9") (pin "2") (pinfunction "2_2") (pintype "passive"))
    )
    (net (code "64") (name "GND") (class "Default")
      (node (ref "C1") (pin "-") (pinfunction "-_-") (pintype "passive"))
      (node (ref "C10") (pin "2") (pinfunction "2_2") (pintype "passive"))
      (node (ref "C12") (pin "2") (pinfunction "2_2") (pintype "passive"))
      (node (ref "C13") (pin "-") (pinfunction "-_-") (pintype "passive"))
      (node (ref "C14") (pin "2") (pinfunction "2_2") (pintype "passive"))
      (node (ref "C15") (pin "2") (pinfunction "2_2") (pintype "passive"))
      (node (ref "C16") (pin "2") (pinfunction "2_2") (pintype "passive"))
      (node (ref "C18") (pin "2") (pinfunction "2_2") (pintype "passive"))
      (node (ref "C19") (pin "2") (pinfunction "2_2") (pintype "passive"))
      (node (ref "C2") (pin "-") (pinfunction "-_-") (pintype "passive"))
      (node (ref "C20") (pin "2") (pinfunction "2_2") (pintype "passive"))
      (node (ref "C22") (pin "2") (pinfunction "2_2") (pintype "passive"))
      (node (ref "C23") (pin "2") (pinfunction "2_2") (pintype "passive"))
      (node (ref "C24") (pin "2") (pinfunction "2_2") (pintype "passive"))
      (node (ref "C25") (pin "2") (pinfunction "2_2") (pintype "passive"))
      (node (ref "C26") (pin "2") (pinfunction "2_2") (pintype "passive"))
      (node (ref "C27") (pin "2") (pinfunction "2_2") (pintype "passive"))
      (node (ref "C3") (pin "2") (pinfunction "2_2") (pintype "passive"))
      (node (ref "C30") (pin "2") (pinfunction "2_2") (pintype "passive"))
      (node (ref "C31") (pin "2") (pinfunction "2_2") (pintype "passive"))
      (node (ref "C33") (pin "2") (pinfunction "2_2") (pintype "passive"))
      (node (ref "C34") (pin "2") (pinfunction "2_2") (pintype "passive"))
      (node (ref "C35") (pin "2") (pinfunction "2_2") (pintype "passive"))
      (node (ref "C36") (pin "2") (pinfunction "2_2") (pintype "passive"))
      (node (ref "C37") (pin "2") (pinfunction "2_2") (pintype "passive"))
      (node (ref "C4") (pin "2") (pinfunction "2_2") (pintype "passive"))
      (node (ref "C41") (pin "2") (pinfunction "2_2") (pintype "passive"))
      (node (ref "C5") (pin "2") (pinfunction "2_2") (pintype "passive"))
      (node (ref "C6") (pin "2") (pinfunction "2_2") (pintype "passive"))
      (node (ref "C8") (pin "2") (pinfunction "2_2") (pintype "passive"))
      (node (ref "C9") (pin "2") (pinfunction "2_2") (pintype "passive"))
      (node (ref "D1") (pin "A") (pinfunction "A_A") (pintype "passive"))
      (node (ref "D2") (pin "A") (pinfunction "A_A") (pintype "passive"))
      (node (ref "D3") (pin "A") (pinfunction "A_A") (pintype "passive"))
      (node (ref "D6") (pin "1") (pinfunction "A_1") (pintype "passive"))
      (node (ref "GREEN") (pin "C") (pinfunction "C_C") (pintype "passive"))
      (node (ref "IC1") (pin "3") (pinfunction "GND_3") (pintype "power_in"))
      (node (ref "J2") (pin "2") (pinfunction "S_2") (pintype "passive"))
      (node (ref "Q1") (pin "2") (pinfunction "S_2") (pintype "passive"))
      (node (ref "Q2") (pin "2") (pinfunction "S_2") (pintype "passive"))
      (node (ref "Q3") (pin "2") (pinfunction "S_2") (pintype "passive"))
      (node (ref "Q4") (pin "2") (pinfunction "S_2") (pintype "passive"))
      (node (ref "R1") (pin "2") (pinfunction "2_2") (pintype "passive"))
      (node (ref "R13") (pin "1") (pinfunction "1_1") (pintype "passive"))
      (node (ref "R14") (pin "1") (pinfunction "1_1") (pintype "passive"))
      (node (ref "R16") (pin "1") (pinfunction "1_1") (pintype "passive"))
      (node (ref "R2") (pin "2") (pinfunction "2_2") (pintype "passive"))
      (node (ref "R20") (pin "1") (pinfunction "1_1") (pintype "passive"))
      (node (ref "R21") (pin "1") (pinfunction "1_1") (pintype "passive"))
      (node (ref "R27") (pin "1") (pinfunction "1_1") (pintype "passive"))
      (node (ref "R29") (pin "1") (pinfunction "1_1") (pintype "passive"))
      (node (ref "R30") (pin "1") (pinfunction "1_1") (pintype "passive"))
      (node (ref "R31") (pin "1") (pinfunction "1_1") (pintype "passive"))
      (node (ref "R32") (pin "1") (pinfunction "1_1") (pintype "passive"))
      (node (ref "R43") (pin "1") (pinfunction "1_1") (pintype "passive"))
      (node (ref "R44") (pin "1") (pinfunction "1_1") (pintype "passive"))
      (node (ref "R45") (pin "1") (pinfunction "1_1") (pintype "passive"))
      (node (ref "R46") (pin "1") (pinfunction "1_1") (pintype "passive"))
      (node (ref "R49") (pin "1") (pinfunction "1_1") (pintype "passive"))
      (node (ref "R5") (pin "2") (pinfunction "2_2") (pintype "passive"))
      (node (ref "RED") (pin "C") (pinfunction "C_C") (pintype "passive"))
      (node (ref "SV1") (pin "4") (pinfunction "4_4") (pintype "passive"))
      (node (ref "U1") (pin "6") (pinfunction "GND_6") (pintype "passive"))
      (node (ref "U1") (pin "9") (pinfunction "POWERPAD_9") (pintype "passive"))
      (node (ref "U2") (pin "6") (pinfunction "GND_6") (pintype "passive"))
      (node (ref "U2") (pin "9") (pinfunction "POWERPAD_9") (pintype "passive"))
      (node (ref "U3") (pin "6") (pinfunction "GND_6") (pintype "passive"))
      (node (ref "U3") (pin "9") (pinfunction "POWERPAD_9") (pintype "passive"))
      (node (ref "U4") (pin "15") (pinfunction "GND_15") (pintype "passive"))
      (node (ref "U5") (pin "2") (pinfunction "GND_2") (pintype "passive"))
      (node (ref "U6") (pin "2") (pinfunction "GND_2") (pintype "passive"))
      (node (ref "U7") (pin "2") (pinfunction "GND_2") (pintype "passive"))
      (node (ref "U8") (pin "2") (pinfunction "GND_2") (pintype "passive"))
    )
    (net (code "65") (name "Net-(U5-REF)") (class "Default")
      (node (ref "R46") (pin "2") (pinfunction "2_2") (pintype "passive"))
      (node (ref "U5") (pin "1") (pinfunction "REF_1") (pintype "input"))
    )
    (net (code "66") (name "Net-(U6-REF)") (class "Default")
      (node (ref "R43") (pin "2") (pinfunction "2_2") (pintype "passive"))
      (node (ref "U6") (pin "1") (pinfunction "REF_1") (pintype "input"))
    )
    (net (code "67") (name "Net-(U7-REF)") (class "Default")
      (node (ref "R45") (pin "2") (pinfunction "2_2") (pintype "passive"))
      (node (ref "U7") (pin "1") (pinfunction "REF_1") (pintype "input"))
    )
    (net (code "68") (name "Net-(U8-REF)") (class "Default")
      (node (ref "R44") (pin "2") (pinfunction "2_2") (pintype "passive"))
      (node (ref "U8") (pin "1") (pinfunction "REF_1") (pintype "input"))
    )
    (net (code "69") (name "unconnected-(JP7-Pad1)") (class "Default")
      (node (ref "JP7") (pin "1") (pinfunction "1_1") (pintype "passive"))
    )
    (net (code "70") (name "unconnected-(JP8-Pad1)") (class "Default")
      (node (ref "JP8") (pin "1") (pinfunction "1_1") (pintype "passive"))
    )
    (net (code "71") (name "unconnected-(SV1-Pad8)") (class "Default")
      (node (ref "SV1") (pin "8") (pinfunction "8_8") (pintype "passive"))
    )
    (net (code "72") (name "unconnected-(SV1-Pad9)") (class "Default")
      (node (ref "SV1") (pin "9") (pinfunction "9_9") (pintype "passive"))
    )
    (net (code "73") (name "unconnected-(SV1-Pad10)") (class "Default")
      (node (ref "SV1") (pin "10") (pinfunction "10_10") (pintype "passive"))
    )
    (net (code "74") (name "unconnected-(SV2-Pad1)") (class "Default")
      (node (ref "SV2") (pin "1") (pinfunction "1_1") (pintype "passive"))
    )
    (net (code "75") (name "unconnected-(SV2-Pad2)") (class "Default")
      (node (ref "SV2") (pin "2") (pinfunction "2_2") (pintype "passive"))
    )
    (net (code "76") (name "unconnected-(SV2-Pad3)") (class "Default")
      (node (ref "SV2") (pin "3") (pinfunction "3_3") (pintype "passive"))
    )
    (net (code "77") (name "unconnected-(SV2-Pad4)") (class "Default")
      (node (ref "SV2") (pin "4") (pinfunction "4_4") (pintype "passive"))
    )
    (net (code "78") (name "unconnected-(SV2-Pad5)") (class "Default")
      (node (ref "SV2") (pin "5") (pinfunction "5_5") (pintype "passive"))
    )
    (net (code "79") (name "unconnected-(SV2-Pad6)") (class "Default")
      (node (ref "SV2") (pin "6") (pinfunction "6_6") (pintype "passive"))
    )
    (net (code "80") (name "unconnected-(SV2-Pad7)") (class "Default")
      (node (ref "SV2") (pin "7") (pinfunction "7_7") (pintype "passive"))
    )
    (net (code "81") (name "unconnected-(SV2-Pad8)") (class "Default")
      (node (ref "SV2") (pin "8") (pinfunction "8_8") (pintype "passive"))
    )
    (net (code "82") (name "unconnected-(SV2-Pad9)") (class "Default")
      (node (ref "SV2") (pin "9") (pinfunction "9_9") (pintype "passive"))
    )
    (net (code "83") (name "unconnected-(SV2-Pad10)") (class "Default")
      (node (ref "SV2") (pin "10") (pinfunction "10_10") (pintype "passive"))
    )
    (net (code "84") (name "unconnected-(U1-NC-Pad2)") (class "Default")
      (node (ref "U1") (pin "2") (pinfunction "NC_2") (pintype "no_connect"))
    )
    (net (code "85") (name "unconnected-(U1-NC_2-Pad3)") (class "Default")
      (node (ref "U1") (pin "3") (pinfunction "NC_2_3") (pintype "no_connect"))
    )
    (net (code "86") (name "unconnected-(U2-NC-Pad2)") (class "Default")
      (node (ref "U2") (pin "2") (pinfunction "NC_2") (pintype "no_connect"))
    )
    (net (code "87") (name "unconnected-(U2-NC_2-Pad3)") (class "Default")
      (node (ref "U2") (pin "3") (pinfunction "NC_2_3") (pintype "no_connect"))
    )
    (net (code "88") (name "unconnected-(U3-NC-Pad2)") (class "Default")
      (node (ref "U3") (pin "2") (pinfunction "NC_2") (pintype "no_connect"))
    )
    (net (code "89") (name "unconnected-(U3-NC_2-Pad3)") (class "Default")
      (node (ref "U3") (pin "3") (pinfunction "NC_2_3") (pintype "no_connect"))
    )
    (net (code "90") (name "unconnected-(U4-AIN8-Pad2)") (class "Default")
      (node (ref "U4") (pin "2") (pinfunction "AIN8_2") (pintype "input"))
    )
    (net (code "91") (name "unconnected-(U4-AIN9-Pad3)") (class "Default")
      (node (ref "U4") (pin "3") (pinfunction "AIN9_3") (pintype "input"))
    )
    (net (code "92") (name "unconnected-(U4-AIN10-Pad4)") (class "Default")
      (node (ref "U4") (pin "4") (pinfunction "AIN10_4") (pintype "input"))
    )
  )
)
